# Agriculture_iot_2020-07-04_16-49-31.net
KiCad netlist of a schematic drawn in EasyEDA
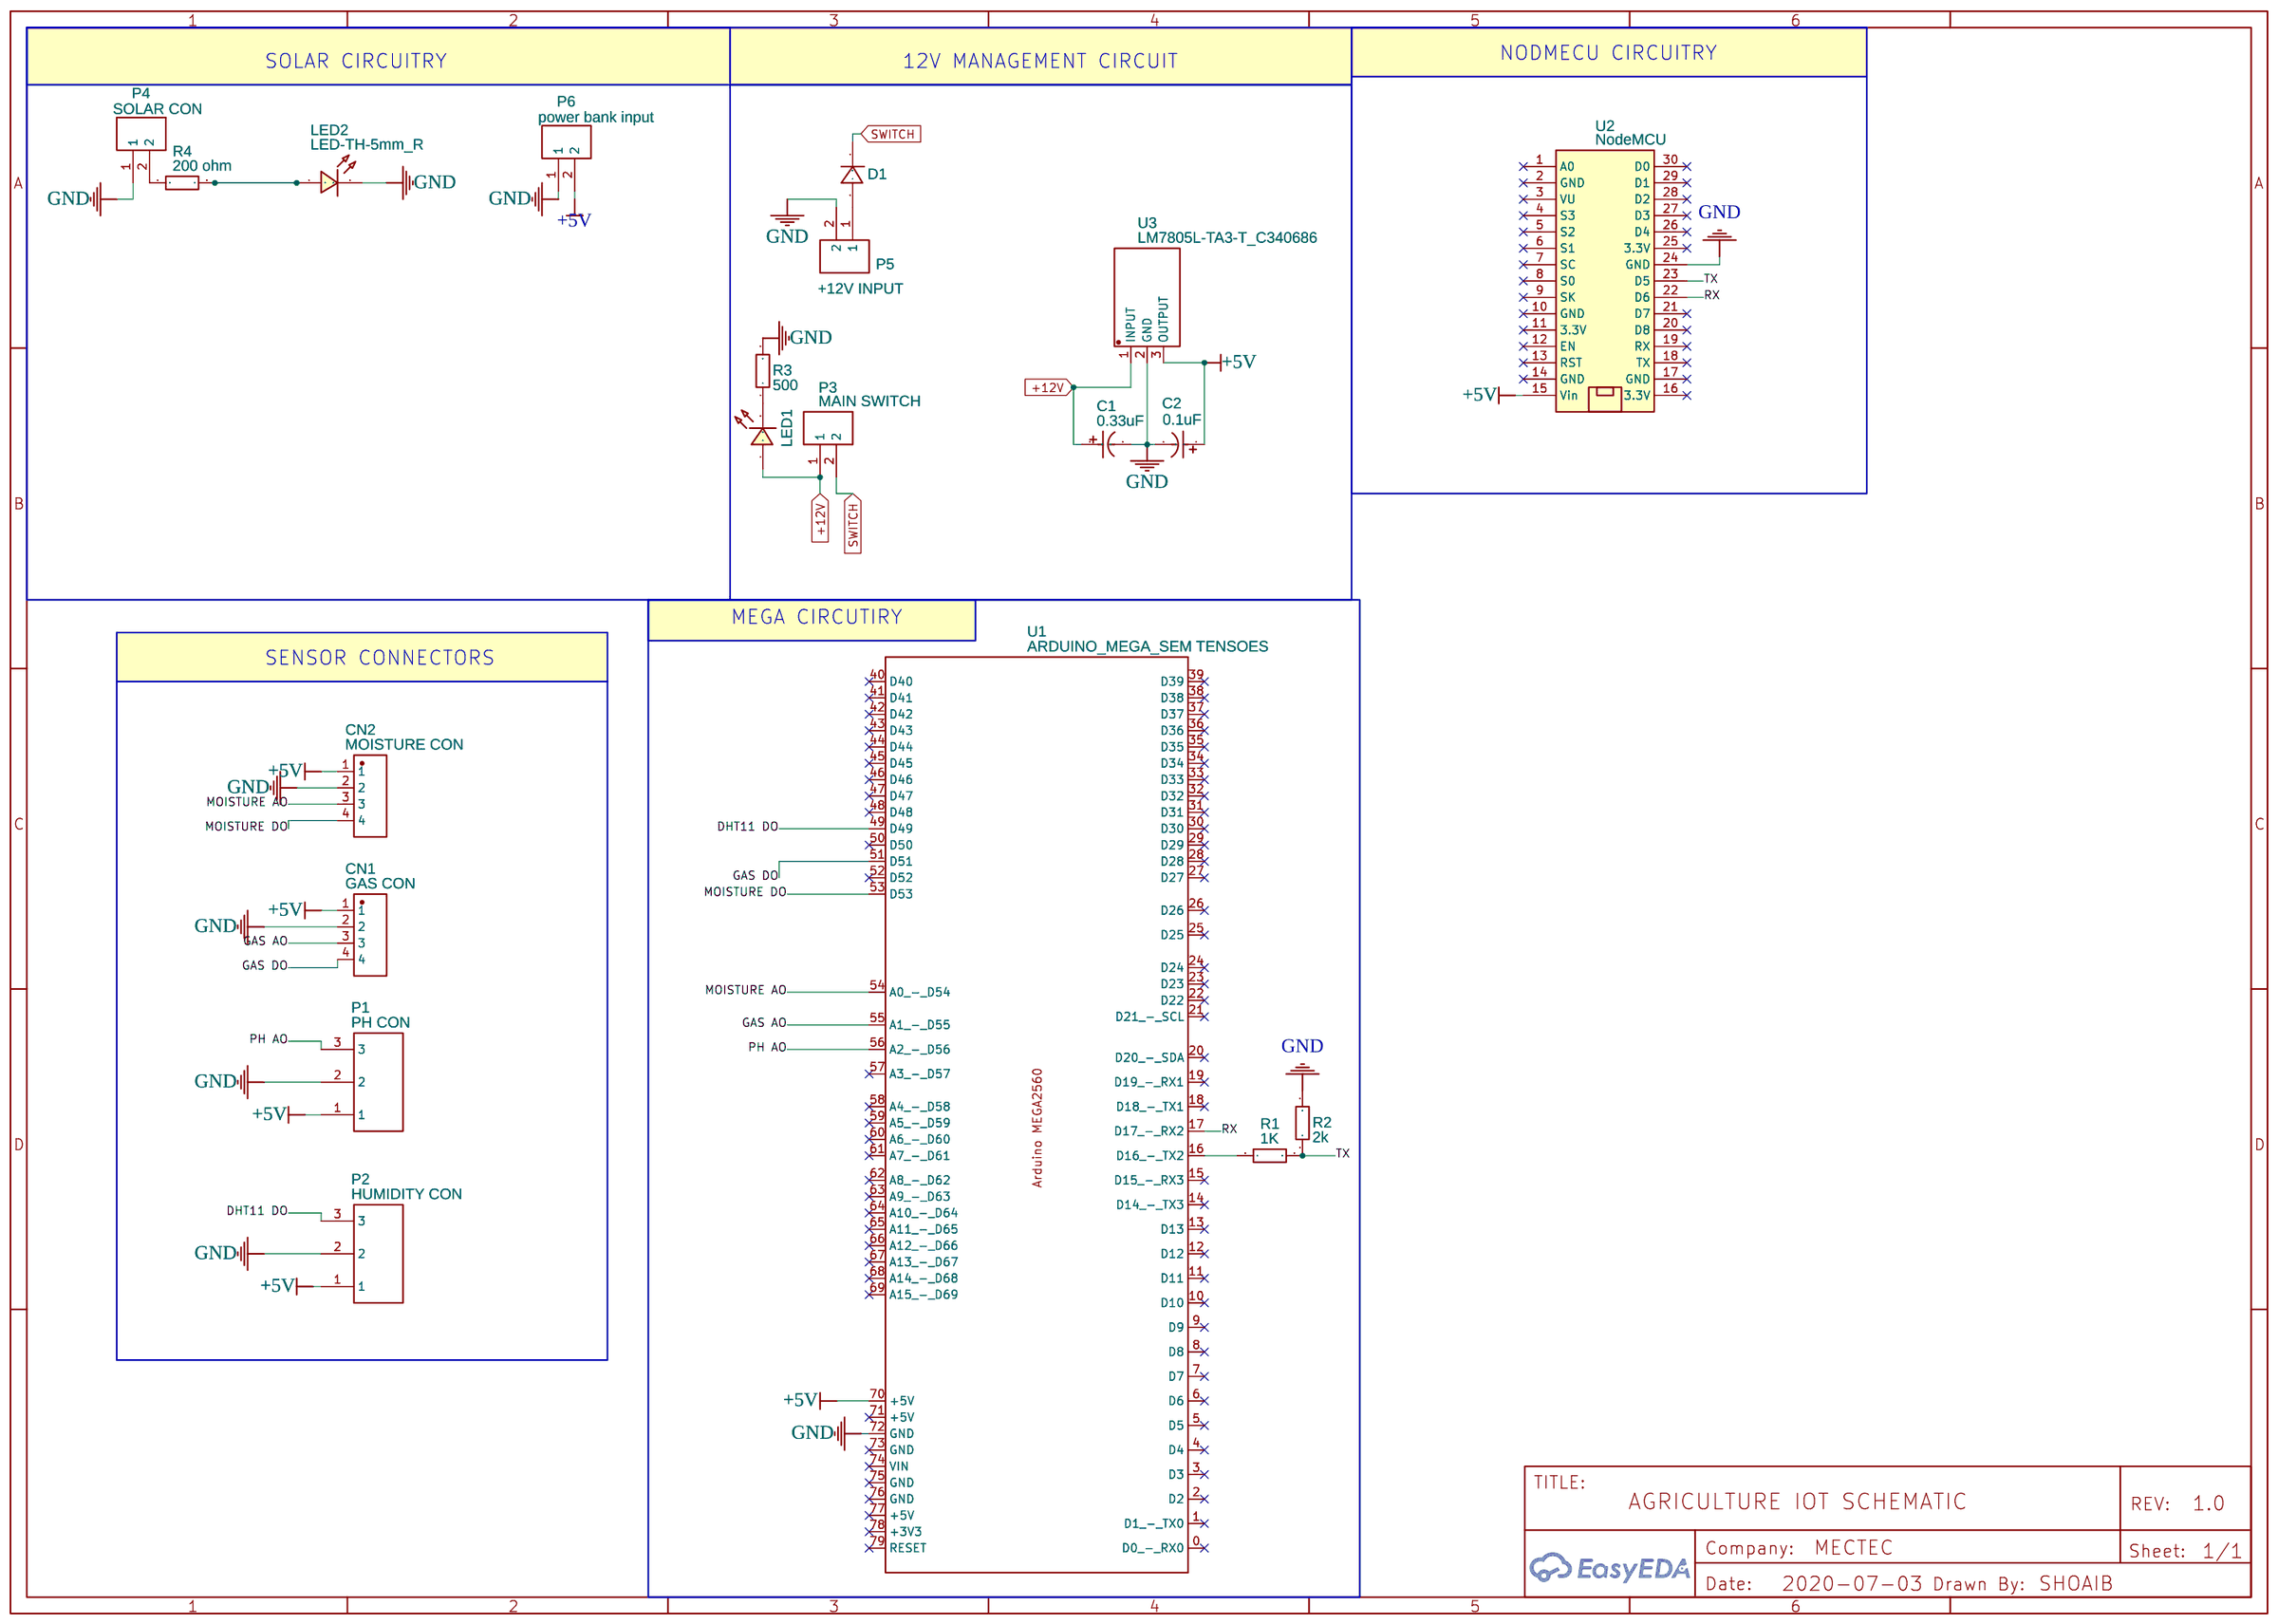
[diagram p0: schematic sheet]

(export (version "E")
  (design (tool "Eeschema 10.0.6"))
  (components
    (comp (ref "C1")
      (value "0.33uF")
      (fields
        (field (name "BOM_Manufacturer Part") "22uF 25V 4*7")
        (field (name "BOM_Supplier Part") "C43840")
      )
      (libsource (lib "") (part "22uF 25V 4*7"))
    )
    (comp (ref "C2")
      (value "0.1uF")
      (fields
        (field (name "BOM_Manufacturer Part") "22uF 25V 4*7")
        (field (name "BOM_Supplier Part") "C43840")
      )
      (libsource (lib "") (part "22uF 25V 4*7_1"))
    )
    (comp (ref "CN1")
      (value "GAS CON")
      (fields
        (field (name "BOM_Manufacturer Part") "WJ127-5.0-4P")
        (field (name "BOM_Supplier Part") "C192779")
      )
      (libsource (lib "") (part "WJ127-5.0-4P"))
    )
    (comp (ref "CN2")
      (value "MOISTURE CON")
      (fields
        (field (name "BOM_Manufacturer Part") "WJ127-5.0-4P")
        (field (name "BOM_Supplier Part") "C192779")
      )
      (libsource (lib "") (part "WJ127-5.0-4P"))
    )
    (comp (ref "D1")
      (value "1N4001_C331627")
      (fields (field (name "BOM_Manufacturer Part") "1N4001") (field (name "BOM_Supplier Part") "C331627"))
      (libsource (lib "") (part "1N4001_C331627"))
    )
    (comp (ref "LED1")
      (value "LED-TH-5mm_R")
      (fields
        (field (name "BOM_Manufacturer Part") "333-2SURD/S530-A3")
        (field (name "BOM_Supplier Part") "C87271")
      )
      (libsource (lib "") (part "LED-TH-5mm_R"))
    )
    (comp (ref "LED2")
      (value "LED-TH-5mm_R")
      (fields
        (field (name "BOM_Manufacturer Part") "333-2SURD/S530-A3")
        (field (name "BOM_Supplier Part") "C87271")
      )
      (libsource (lib "") (part "LED-TH-5mm_R_1"))
    )
    (comp (ref "P1")
      (value "PH CON")
      (fields
        (field (name "BOM_Manufacturer Part") "WJ301V-5.0-3P")
        (field (name "BOM_Supplier Part") "C8483")
      )
      (libsource (lib "") (part "WJ301V-5.0-3P"))
    )
    (comp (ref "P2")
      (value "HUMIDITY CON")
      (fields
        (field (name "BOM_Manufacturer Part") "WJ301V-5.0-3P")
        (field (name "BOM_Supplier Part") "C8483")
      )
      (libsource (lib "") (part "WJ301V-5.0-3P"))
    )
    (comp (ref "P3")
      (value "MAIN SWITCH")
      (fields
        (field (name "BOM_Manufacturer Part") "WJ301V-5.0-2P")
        (field (name "BOM_Supplier Part") "C8475")
      )
      (libsource (lib "") (part "WJ301V-5.0-2P"))
    )
    (comp (ref "P4")
      (value "SOLAR CON")
      (fields
        (field (name "BOM_Manufacturer Part") "WJ301V-5.0-2P")
        (field (name "BOM_Supplier Part") "C8475")
      )
      (libsource (lib "") (part "WJ301V-5.0-2P"))
    )
    (comp (ref "P5")
      (value "+12V INPUT")
      (fields
        (field (name "BOM_Manufacturer Part") "WJ301V-5.0-2P")
        (field (name "BOM_Supplier Part") "C8475")
      )
      (libsource (lib "") (part "WJ301V-5.0-2P_1"))
    )
    (comp (ref "P6")
      (value "power bank input")
      (fields
        (field (name "BOM_Manufacturer Part") "WJ301V-5.0-2P")
        (field (name "BOM_Supplier Part") "C8475")
      )
      (libsource (lib "") (part "WJ301V-5.0-2P"))
    )
    (comp (ref "R1")
      (value "1K")
      (fields (field (name "BOM_Supplier Part") "C120055"))
      (libsource (lib "") (part "CF1/4W-1KΩ±5% T52_1"))
    )
    (comp (ref "R2")
      (value "2k")
      (fields (field (name "BOM_Supplier Part") "C120055"))
      (libsource (lib "") (part "CF1/4W-1KΩ±5% T52"))
    )
    (comp (ref "R3")
      (value "500")
      (fields (field (name "BOM_Supplier Part") "C120055"))
      (libsource (lib "") (part "CF1/4W-1KΩ±5% T52"))
    )
    (comp (ref "R4")
      (value "200 ohm")
      (fields (field (name "BOM_Supplier Part") "C120055"))
      (libsource (lib "") (part "CF1/4W-1KΩ±5% T52_1"))
    )
    (comp (ref "U1")
      (value "ARDUINO_MEGA_SEM TENSOES")
      (fields (field (name "BOM_Manufacturer Part") "ArduinoMega2560"))
      (libsource (lib "") (part "ARDUINO_MEGA_SEM TENSOES"))
    )
    (comp (ref "U2")
      (value "NodeMCU")
      (fields (field (name "BOM_Manufacturer Part") "NodeMcu V3 LoLin"))
      (libsource (lib "") (part "NodeMCU"))
    )
    (comp (ref "U3")
      (value "LM7805L-TA3-T_C340686")
      (fields
        (field (name "BOM_Manufacturer Part") "LM7805L-TA3-T")
        (field (name "BOM_Supplier Part") "C340686")
      )
      (libsource (lib "") (part "LM7805L-TA3-T_C340686"))
    )
  )
  (nets
    (net (code "1") (name "+5V") (class "Default")
      (node (ref "C2") (pin "1") (pinfunction "1_1") (pintype "input"))
      (node (ref "CN1") (pin "1") (pinfunction "1_1") (pintype "unspecified"))
      (node (ref "CN2") (pin "1") (pinfunction "1_1") (pintype "unspecified"))
      (node (ref "P1") (pin "1") (pinfunction "1_1") (pintype "unspecified"))
      (node (ref "P2") (pin "1") (pinfunction "1_1") (pintype "unspecified"))
      (node (ref "P6") (pin "2") (pinfunction "2_2") (pintype "unspecified"))
      (node (ref "U1") (pin "70") (pinfunction "+5V_70") (pintype "unspecified"))
      (node (ref "U2") (pin "15") (pinfunction "Vin_15") (pintype "unspecified"))
      (node (ref "U3") (pin "3") (pinfunction "OUTPUT_3") (pintype "unspecified"))
    )
    (net (code "2") (name "+12V") (class "Default")
      (node (ref "C1") (pin "1") (pinfunction "1_1") (pintype "input"))
      (node (ref "LED1") (pin "1") (pinfunction "1_1") (pintype "unspecified"))
      (node (ref "P3") (pin "1") (pinfunction "1_1") (pintype "unspecified"))
      (node (ref "U3") (pin "1") (pinfunction "INPUT_1") (pintype "unspecified"))
    )
    (net (code "3") (name "/DHT11 DO") (class "Default")
      (node (ref "P2") (pin "3") (pinfunction "3_3") (pintype "unspecified"))
      (node (ref "U1") (pin "49") (pinfunction "D49_49") (pintype "unspecified"))
    )
    (net (code "4") (name "/GAS AO") (class "Default")
      (node (ref "CN1") (pin "3") (pinfunction "3_3") (pintype "unspecified"))
      (node (ref "U1") (pin "55") (pinfunction "A1_-_D55_55") (pintype "unspecified"))
    )
    (net (code "5") (name "/GAS DO") (class "Default")
      (node (ref "CN1") (pin "4") (pinfunction "4_4") (pintype "unspecified"))
      (node (ref "U1") (pin "51") (pinfunction "D51_51") (pintype "unspecified"))
    )
    (net (code "6") (name "/MOISTURE AO") (class "Default")
      (node (ref "CN2") (pin "3") (pinfunction "3_3") (pintype "unspecified"))
      (node (ref "U1") (pin "54") (pinfunction "A0_-_D54_54") (pintype "unspecified"))
    )
    (net (code "7") (name "/MOISTURE DO") (class "Default")
      (node (ref "CN2") (pin "4") (pinfunction "4_4") (pintype "unspecified"))
      (node (ref "U1") (pin "53") (pinfunction "D53_53") (pintype "unspecified"))
    )
    (net (code "8") (name "/PH AO") (class "Default")
      (node (ref "P1") (pin "3") (pinfunction "3_3") (pintype "unspecified"))
      (node (ref "U1") (pin "56") (pinfunction "A2_-_D56_56") (pintype "unspecified"))
    )
    (net (code "9") (name "/RX") (class "Default")
      (node (ref "U1") (pin "17") (pinfunction "D17_-_RX2_17") (pintype "unspecified"))
      (node (ref "U2") (pin "22") (pinfunction "D6_22") (pintype "unspecified"))
    )
    (net (code "10") (name "/TX") (class "Default")
      (node (ref "R1") (pin "2") (pinfunction "2_2") (pintype "unspecified"))
      (node (ref "R2") (pin "1") (pinfunction "1_1") (pintype "unspecified"))
      (node (ref "U2") (pin "23") (pinfunction "D5_23") (pintype "unspecified"))
    )
    (net (code "11") (name "GND") (class "Default")
      (node (ref "C1") (pin "2") (pinfunction "2_2") (pintype "input"))
      (node (ref "C2") (pin "2") (pinfunction "2_2") (pintype "input"))
      (node (ref "CN1") (pin "2") (pinfunction "2_2") (pintype "unspecified"))
      (node (ref "CN2") (pin "2") (pinfunction "2_2") (pintype "unspecified"))
      (node (ref "LED2") (pin "2") (pinfunction "2_2") (pintype "unspecified"))
      (node (ref "P1") (pin "2") (pinfunction "2_2") (pintype "unspecified"))
      (node (ref "P2") (pin "2") (pinfunction "2_2") (pintype "unspecified"))
      (node (ref "P4") (pin "1") (pinfunction "1_1") (pintype "unspecified"))
      (node (ref "P5") (pin "2") (pinfunction "2_2") (pintype "unspecified"))
      (node (ref "P6") (pin "1") (pinfunction "1_1") (pintype "unspecified"))
      (node (ref "R2") (pin "2") (pinfunction "2_2") (pintype "unspecified"))
      (node (ref "R3") (pin "2") (pinfunction "2_2") (pintype "unspecified"))
      (node (ref "U1") (pin "72") (pinfunction "GND_72") (pintype "unspecified"))
      (node (ref "U2") (pin "24") (pinfunction "GND_24") (pintype "unspecified"))
      (node (ref "U3") (pin "2") (pinfunction "GND_2") (pintype "unspecified"))
    )
    (net (code "12") (name "Net-(D1-A)") (class "Default")
      (node (ref "D1") (pin "2") (pinfunction "A_2") (pintype "unspecified"))
      (node (ref "P5") (pin "1") (pinfunction "1_1") (pintype "unspecified"))
    )
    (net (code "13") (name "Net-(LED1-Pad2)") (class "Default")
      (node (ref "LED1") (pin "2") (pinfunction "2_2") (pintype "unspecified"))
      (node (ref "R3") (pin "1") (pinfunction "1_1") (pintype "unspecified"))
    )
    (net (code "14") (name "Net-(LED2-Pad1)") (class "Default")
      (node (ref "LED2") (pin "1") (pinfunction "1_1") (pintype "unspecified"))
      (node (ref "R4") (pin "2") (pinfunction "2_2") (pintype "unspecified"))
    )
    (net (code "15") (name "Net-(P4-Pad2)") (class "Default")
      (node (ref "P4") (pin "2") (pinfunction "2_2") (pintype "unspecified"))
      (node (ref "R4") (pin "1") (pinfunction "1_1") (pintype "unspecified"))
    )
    (net (code "16") (name "Net-(U1-D16_-_TX2)") (class "Default")
      (node (ref "R1") (pin "1") (pinfunction "1_1") (pintype "unspecified"))
      (node (ref "U1") (pin "16") (pinfunction "D16_-_TX2_16") (pintype "unspecified"))
    )
    (net (code "17") (name "SWITCH") (class "Default")
      (node (ref "D1") (pin "1") (pinfunction "C_1") (pintype "unspecified"))
      (node (ref "P3") (pin "2") (pinfunction "2_2") (pintype "unspecified"))
    )
    (net (code "18") (name "unconnected-(U1-+3V3-Pad78)") (class "Default")
      (node (ref "U1") (pin "78") (pinfunction "+3V3_78") (pintype "unspecified+no_connect"))
    )
    (net (code "19") (name "unconnected-(U1-+5V-Pad71)") (class "Default")
      (node (ref "U1") (pin "71") (pinfunction "+5V_71") (pintype "unspecified+no_connect"))
    )
    (net (code "20") (name "unconnected-(U1-+5V-Pad77)") (class "Default")
      (node (ref "U1") (pin "77") (pinfunction "+5V_77") (pintype "unspecified+no_connect"))
    )
    (net (code "21") (name "unconnected-(U1-A3_-_D57-Pad57)") (class "Default")
      (node (ref "U1") (pin "57") (pinfunction "A3_-_D57_57") (pintype "unspecified+no_connect"))
    )
    (net (code "22") (name "unconnected-(U1-A4_-_D58-Pad58)") (class "Default")
      (node (ref "U1") (pin "58") (pinfunction "A4_-_D58_58") (pintype "unspecified+no_connect"))
    )
    (net (code "23") (name "unconnected-(U1-A5_-_D59-Pad59)") (class "Default")
      (node (ref "U1") (pin "59") (pinfunction "A5_-_D59_59") (pintype "unspecified+no_connect"))
    )
    (net (code "24") (name "unconnected-(U1-A6_-_D60-Pad60)") (class "Default")
      (node (ref "U1") (pin "60") (pinfunction "A6_-_D60_60") (pintype "unspecified+no_connect"))
    )
    (net (code "25") (name "unconnected-(U1-A7_-_D61-Pad61)") (class "Default")
      (node (ref "U1") (pin "61") (pinfunction "A7_-_D61_61") (pintype "unspecified+no_connect"))
    )
    (net (code "26") (name "unconnected-(U1-A8_-_D62-Pad62)") (class "Default")
      (node (ref "U1") (pin "62") (pinfunction "A8_-_D62_62") (pintype "unspecified+no_connect"))
    )
    (net (code "27") (name "unconnected-(U1-A9_-_D63-Pad63)") (class "Default")
      (node (ref "U1") (pin "63") (pinfunction "A9_-_D63_63") (pintype "unspecified+no_connect"))
    )
    (net (code "28") (name "unconnected-(U1-A10_-_D64-Pad64)") (class "Default")
      (node (ref "U1") (pin "64") (pinfunction "A10_-_D64_64") (pintype "unspecified+no_connect"))
    )
    (net (code "29") (name "unconnected-(U1-A11_-_D65-Pad65)") (class "Default")
      (node (ref "U1") (pin "65") (pinfunction "A11_-_D65_65") (pintype "unspecified+no_connect"))
    )
    (net (code "30") (name "unconnected-(U1-A12_-_D66-Pad66)") (class "Default")
      (node (ref "U1") (pin "66") (pinfunction "A12_-_D66_66") (pintype "unspecified+no_connect"))
    )
    (net (code "31") (name "unconnected-(U1-A13_-_D67-Pad67)") (class "Default")
      (node (ref "U1") (pin "67") (pinfunction "A13_-_D67_67") (pintype "unspecified+no_connect"))
    )
    (net (code "32") (name "unconnected-(U1-A14_-_D68-Pad68)") (class "Default")
      (node (ref "U1") (pin "68") (pinfunction "A14_-_D68_68") (pintype "unspecified+no_connect"))
    )
    (net (code "33") (name "unconnected-(U1-A15_-_D69-Pad69)") (class "Default")
      (node (ref "U1") (pin "69") (pinfunction "A15_-_D69_69") (pintype "unspecified+no_connect"))
    )
    (net (code "34") (name "unconnected-(U1-D0_-_RX0-Pad0)") (class "Default")
      (node (ref "U1") (pin "0") (pinfunction "D0_-_RX0_0") (pintype "unspecified+no_connect"))
    )
    (net (code "35") (name "unconnected-(U1-D1_-_TX0-Pad1)") (class "Default")
      (node (ref "U1") (pin "1") (pinfunction "D1_-_TX0_1") (pintype "unspecified+no_connect"))
    )
    (net (code "36") (name "unconnected-(U1-D2-Pad2)") (class "Default")
      (node (ref "U1") (pin "2") (pinfunction "D2_2") (pintype "unspecified+no_connect"))
    )
    (net (code "37") (name "unconnected-(U1-D3-Pad3)") (class "Default")
      (node (ref "U1") (pin "3") (pinfunction "D3_3") (pintype "unspecified+no_connect"))
    )
    (net (code "38") (name "unconnected-(U1-D4-Pad4)") (class "Default")
      (node (ref "U1") (pin "4") (pinfunction "D4_4") (pintype "unspecified+no_connect"))
    )
    (net (code "39") (name "unconnected-(U1-D5-Pad5)") (class "Default")
      (node (ref "U1") (pin "5") (pinfunction "D5_5") (pintype "unspecified+no_connect"))
    )
    (net (code "40") (name "unconnected-(U1-D6-Pad6)") (class "Default")
      (node (ref "U1") (pin "6") (pinfunction "D6_6") (pintype "unspecified+no_connect"))
    )
    (net (code "41") (name "unconnected-(U1-D7-Pad7)") (class "Default")
      (node (ref "U1") (pin "7") (pinfunction "D7_7") (pintype "unspecified+no_connect"))
    )
    (net (code "42") (name "unconnected-(U1-D8-Pad8)") (class "Default")
      (node (ref "U1") (pin "8") (pinfunction "D8_8") (pintype "unspecified+no_connect"))
    )
    (net (code "43") (name "unconnected-(U1-D9-Pad9)") (class "Default")
      (node (ref "U1") (pin "9") (pinfunction "D9_9") (pintype "unspecified+no_connect"))
    )
    (net (code "44") (name "unconnected-(U1-D10-Pad10)") (class "Default")
      (node (ref "U1") (pin "10") (pinfunction "D10_10") (pintype "unspecified+no_connect"))
    )
    (net (code "45") (name "unconnected-(U1-D11-Pad11)") (class "Default")
      (node (ref "U1") (pin "11") (pinfunction "D11_11") (pintype "unspecified+no_connect"))
    )
    (net (code "46") (name "unconnected-(U1-D12-Pad12)") (class "Default")
      (node (ref "U1") (pin "12") (pinfunction "D12_12") (pintype "unspecified+no_connect"))
    )
    (net (code "47") (name "unconnected-(U1-D13-Pad13)") (class "Default")
      (node (ref "U1") (pin "13") (pinfunction "D13_13") (pintype "unspecified+no_connect"))
    )
    (net (code "48") (name "unconnected-(U1-D14_-_TX3-Pad14)") (class "Default")
      (node (ref "U1") (pin "14") (pinfunction "D14_-_TX3_14") (pintype "unspecified+no_connect"))
    )
    (net (code "49") (name "unconnected-(U1-D15_-_RX3-Pad15)") (class "Default")
      (node (ref "U1") (pin "15") (pinfunction "D15_-_RX3_15") (pintype "unspecified+no_connect"))
    )
    (net (code "50") (name "unconnected-(U1-D18_-_TX1-Pad18)") (class "Default")
      (node (ref "U1") (pin "18") (pinfunction "D18_-_TX1_18") (pintype "unspecified+no_connect"))
    )
    (net (code "51") (name "unconnected-(U1-D19_-_RX1-Pad19)") (class "Default")
      (node (ref "U1") (pin "19") (pinfunction "D19_-_RX1_19") (pintype "unspecified+no_connect"))
    )
    (net (code "52") (name "unconnected-(U1-D20_-_SDA-Pad20)") (class "Default")
      (node (ref "U1") (pin "20") (pinfunction "D20_-_SDA_20") (pintype "unspecified+no_connect"))
    )
    (net (code "53") (name "unconnected-(U1-D21_-_SCL-Pad21)") (class "Default")
      (node (ref "U1") (pin "21") (pinfunction "D21_-_SCL_21") (pintype "unspecified+no_connect"))
    )
    (net (code "54") (name "unconnected-(U1-D22-Pad22)") (class "Default")
      (node (ref "U1") (pin "22") (pinfunction "D22_22") (pintype "unspecified+no_connect"))
    )
    (net (code "55") (name "unconnected-(U1-D23-Pad23)") (class "Default")
      (node (ref "U1") (pin "23") (pinfunction "D23_23") (pintype "unspecified+no_connect"))
    )
    (net (code "56") (name "unconnected-(U1-D24-Pad24)") (class "Default")
      (node (ref "U1") (pin "24") (pinfunction "D24_24") (pintype "unspecified+no_connect"))
    )
    (net (code "57") (name "unconnected-(U1-D25-Pad25)") (class "Default")
      (node (ref "U1") (pin "25") (pinfunction "D25_25") (pintype "unspecified+no_connect"))
    )
    (net (code "58") (name "unconnected-(U1-D26-Pad26)") (class "Default")
      (node (ref "U1") (pin "26") (pinfunction "D26_26") (pintype "unspecified+no_connect"))
    )
    (net (code "59") (name "unconnected-(U1-D27-Pad27)") (class "Default")
      (node (ref "U1") (pin "27") (pinfunction "D27_27") (pintype "unspecified+no_connect"))
    )
    (net (code "60") (name "unconnected-(U1-D28-Pad28)") (class "Default")
      (node (ref "U1") (pin "28") (pinfunction "D28_28") (pintype "unspecified+no_connect"))
    )
    (net (code "61") (name "unconnected-(U1-D29-Pad29)") (class "Default")
      (node (ref "U1") (pin "29") (pinfunction "D29_29") (pintype "unspecified+no_connect"))
    )
    (net (code "62") (name "unconnected-(U1-D30-Pad30)") (class "Default")
      (node (ref "U1") (pin "30") (pinfunction "D30_30") (pintype "unspecified+no_connect"))
    )
    (net (code "63") (name "unconnected-(U1-D31-Pad31)") (class "Default")
      (node (ref "U1") (pin "31") (pinfunction "D31_31") (pintype "unspecified+no_connect"))
    )
    (net (code "64") (name "unconnected-(U1-D32-Pad32)") (class "Default")
      (node (ref "U1") (pin "32") (pinfunction "D32_32") (pintype "unspecified+no_connect"))
    )
    (net (code "65") (name "unconnected-(U1-D33-Pad33)") (class "Default")
      (node (ref "U1") (pin "33") (pinfunction "D33_33") (pintype "unspecified+no_connect"))
    )
    (net (code "66") (name "unconnected-(U1-D34-Pad34)") (class "Default")
      (node (ref "U1") (pin "34") (pinfunction "D34_34") (pintype "unspecified+no_connect"))
    )
    (net (code "67") (name "unconnected-(U1-D35-Pad35)") (class "Default")
      (node (ref "U1") (pin "35") (pinfunction "D35_35") (pintype "unspecified+no_connect"))
    )
    (net (code "68") (name "unconnected-(U1-D36-Pad36)") (class "Default")
      (node (ref "U1") (pin "36") (pinfunction "D36_36") (pintype "unspecified+no_connect"))
    )
    (net (code "69") (name "unconnected-(U1-D37-Pad37)") (class "Default")
      (node (ref "U1") (pin "37") (pinfunction "D37_37") (pintype "unspecified+no_connect"))
    )
    (net (code "70") (name "unconnected-(U1-D38-Pad38)") (class "Default")
      (node (ref "U1") (pin "38") (pinfunction "D38_38") (pintype "unspecified+no_connect"))
    )
    (net (code "71") (name "unconnected-(U1-D39-Pad39)") (class "Default")
      (node (ref "U1") (pin "39") (pinfunction "D39_39") (pintype "unspecified+no_connect"))
    )
    (net (code "72") (name "unconnected-(U1-D40-Pad40)") (class "Default")
      (node (ref "U1") (pin "40") (pinfunction "D40_40") (pintype "unspecified+no_connect"))
    )
    (net (code "73") (name "unconnected-(U1-D41-Pad41)") (class "Default")
      (node (ref "U1") (pin "41") (pinfunction "D41_41") (pintype "unspecified+no_connect"))
    )
    (net (code "74") (name "unconnected-(U1-D42-Pad42)") (class "Default")
      (node (ref "U1") (pin "42") (pinfunction "D42_42") (pintype "unspecified+no_connect"))
    )
    (net (code "75") (name "unconnected-(U1-D43-Pad43)") (class "Default")
      (node (ref "U1") (pin "43") (pinfunction "D43_43") (pintype "unspecified+no_connect"))
    )
    (net (code "76") (name "unconnected-(U1-D44-Pad44)") (class "Default")
      (node (ref "U1") (pin "44") (pinfunction "D44_44") (pintype "unspecified+no_connect"))
    )
    (net (code "77") (name "unconnected-(U1-D45-Pad45)") (class "Default")
      (node (ref "U1") (pin "45") (pinfunction "D45_45") (pintype "unspecified+no_connect"))
    )
    (net (code "78") (name "unconnected-(U1-D46-Pad46)") (class "Default")
      (node (ref "U1") (pin "46") (pinfunction "D46_46") (pintype "unspecified+no_connect"))
    )
    (net (code "79") (name "unconnected-(U1-D47-Pad47)") (class "Default")
      (node (ref "U1") (pin "47") (pinfunction "D47_47") (pintype "unspecified+no_connect"))
    )
    (net (code "80") (name "unconnected-(U1-D48-Pad48)") (class "Default")
      (node (ref "U1") (pin "48") (pinfunction "D48_48") (pintype "unspecified+no_connect"))
    )
    (net (code "81") (name "unconnected-(U1-D50-Pad50)") (class "Default")
      (node (ref "U1") (pin "50") (pinfunction "D50_50") (pintype "unspecified+no_connect"))
    )
    (net (code "82") (name "unconnected-(U1-D52-Pad52)") (class "Default")
      (node (ref "U1") (pin "52") (pinfunction "D52_52") (pintype "unspecified+no_connect"))
    )
    (net (code "83") (name "unconnected-(U1-GND-Pad73)") (class "Default")
      (node (ref "U1") (pin "73") (pinfunction "GND_73") (pintype "unspecified+no_connect"))
    )
    (net (code "84") (name "unconnected-(U1-GND-Pad75)") (class "Default")
      (node (ref "U1") (pin "75") (pinfunction "GND_75") (pintype "unspecified+no_connect"))
    )
    (net (code "85") (name "unconnected-(U1-GND-Pad76)") (class "Default")
      (node (ref "U1") (pin "76") (pinfunction "GND_76") (pintype "unspecified+no_connect"))
    )
    (net (code "86") (name "unconnected-(U1-RESET-Pad79)") (class "Default")
      (node (ref "U1") (pin "79") (pinfunction "RESET_79") (pintype "unspecified+no_connect"))
    )
    (net (code "87") (name "unconnected-(U1-VIN-Pad74)") (class "Default")
      (node (ref "U1") (pin "74") (pinfunction "VIN_74") (pintype "unspecified+no_connect"))
    )
    (net (code "88") (name "unconnected-(U2-3.3V-Pad11)") (class "Default")
      (node (ref "U2") (pin "11") (pinfunction "3.3V_11") (pintype "unspecified+no_connect"))
    )
    (net (code "89") (name "unconnected-(U2-3.3V-Pad16)") (class "Default")
      (node (ref "U2") (pin "16") (pinfunction "3.3V_16") (pintype "unspecified+no_connect"))
    )
    (net (code "90") (name "unconnected-(U2-3.3V-Pad25)") (class "Default")
      (node (ref "U2") (pin "25") (pinfunction "3.3V_25") (pintype "unspecified+no_connect"))
    )
    (net (code "91") (name "unconnected-(U2-A0-Pad1)") (class "Default")
      (node (ref "U2") (pin "1") (pinfunction "A0_1") (pintype "unspecified+no_connect"))
    )
    (net (code "92") (name "unconnected-(U2-D0-Pad30)") (class "Default")
      (node (ref "U2") (pin "30") (pinfunction "D0_30") (pintype "unspecified+no_connect"))
    )
    (net (code "93") (name "unconnected-(U2-D1-Pad29)") (class "Default")
      (node (ref "U2") (pin "29") (pinfunction "D1_29") (pintype "unspecified+no_connect"))
    )
    (net (code "94") (name "unconnected-(U2-D2-Pad28)") (class "Default")
      (node (ref "U2") (pin "28") (pinfunction "D2_28") (pintype "unspecified+no_connect"))
    )
    (net (code "95") (name "unconnected-(U2-D3-Pad27)") (class "Default")
      (node (ref "U2") (pin "27") (pinfunction "D3_27") (pintype "unspecified+no_connect"))
    )
    (net (code "96") (name "unconnected-(U2-D4-Pad26)") (class "Default")
      (node (ref "U2") (pin "26") (pinfunction "D4_26") (pintype "unspecified+no_connect"))
    )
    (net (code "97") (name "unconnected-(U2-D7-Pad21)") (class "Default")
      (node (ref "U2") (pin "21") (pinfunction "D7_21") (pintype "unspecified+no_connect"))
    )
    (net (code "98") (name "unconnected-(U2-D8-Pad20)") (class "Default")
      (node (ref "U2") (pin "20") (pinfunction "D8_20") (pintype "unspecified+no_connect"))
    )
    (net (code "99") (name "unconnected-(U2-EN-Pad12)") (class "Default")
      (node (ref "U2") (pin "12") (pinfunction "EN_12") (pintype "unspecified+no_connect"))
    )
    (net (code "100") (name "unconnected-(U2-GND-Pad2)") (class "Default")
      (node (ref "U2") (pin "2") (pinfunction "GND_2") (pintype "unspecified+no_connect"))
    )
    (net (code "101") (name "unconnected-(U2-GND-Pad10)") (class "Default")
      (node (ref "U2") (pin "10") (pinfunction "GND_10") (pintype "unspecified+no_connect"))
    )
    (net (code "102") (name "unconnected-(U2-GND-Pad14)") (class "Default")
      (node (ref "U2") (pin "14") (pinfunction "GND_14") (pintype "unspecified+no_connect"))
    )
    (net (code "103") (name "unconnected-(U2-GND-Pad17)") (class "Default")
      (node (ref "U2") (pin "17") (pinfunction "GND_17") (pintype "unspecified+no_connect"))
    )
    (net (code "104") (name "unconnected-(U2-RST-Pad13)") (class "Default")
      (node (ref "U2") (pin "13") (pinfunction "RST_13") (pintype "unspecified+no_connect"))
    )
    (net (code "105") (name "unconnected-(U2-RX-Pad19)") (class "Default")
      (node (ref "U2") (pin "19") (pinfunction "RX_19") (pintype "unspecified+no_connect"))
    )
    (net (code "106") (name "unconnected-(U2-S0-Pad8)") (class "Default")
      (node (ref "U2") (pin "8") (pinfunction "S0_8") (pintype "unspecified+no_connect"))
    )
    (net (code "107") (name "unconnected-(U2-S1-Pad6)") (class "Default")
      (node (ref "U2") (pin "6") (pinfunction "S1_6") (pintype "unspecified+no_connect"))
    )
    (net (code "108") (name "unconnected-(U2-S2-Pad5)") (class "Default")
      (node (ref "U2") (pin "5") (pinfunction "S2_5") (pintype "unspecified+no_connect"))
    )
    (net (code "109") (name "unconnected-(U2-S3-Pad4)") (class "Default")
      (node (ref "U2") (pin "4") (pinfunction "S3_4") (pintype "unspecified+no_connect"))
    )
    (net (code "110") (name "unconnected-(U2-SC-Pad7)") (class "Default")
      (node (ref "U2") (pin "7") (pinfunction "SC_7") (pintype "unspecified+no_connect"))
    )
    (net (code "111") (name "unconnected-(U2-SK-Pad9)") (class "Default")
      (node (ref "U2") (pin "9") (pinfunction "SK_9") (pintype "unspecified+no_connect"))
    )
    (net (code "112") (name "unconnected-(U2-TX-Pad18)") (class "Default")
      (node (ref "U2") (pin "18") (pinfunction "TX_18") (pintype "unspecified+no_connect"))
    )
    (net (code "113") (name "unconnected-(U2-VU-Pad3)") (class "Default")
      (node (ref "U2") (pin "3") (pinfunction "VU_3") (pintype "unspecified+no_connect"))
    )
  )
)
